# SATA.net
KiCad netlist of a schematic drawn in Altium Designer
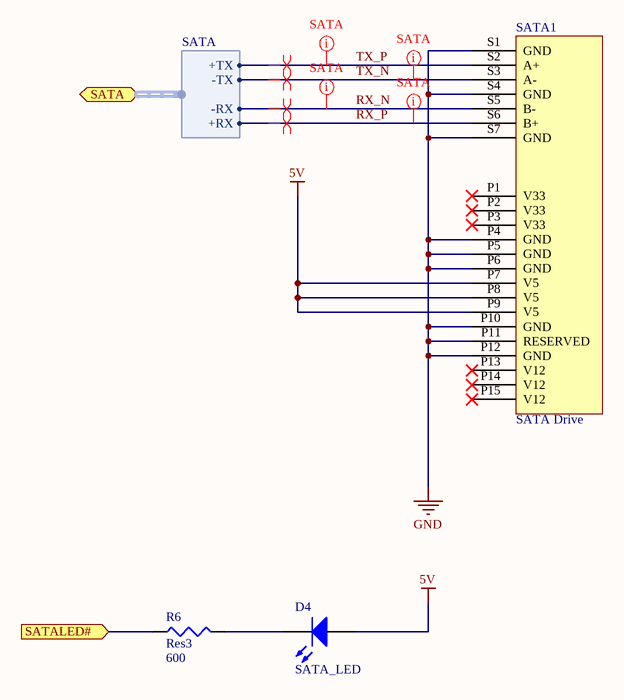
[diagram p0: SATA.SchDoc]

(export (version "E")
  (design (tool "Eeschema 10.0.6"))
  (components
    (comp (ref "D4")
      (value "SATA_LED")
      (footprint "0805")
      (description "Typical RED GaAs LED")
      (fields (field (name "PUBLISHER") "Altium Limited"))
      (libsource (lib "Miscellaneous Devices") (part "LED1"))
    )
    (comp (ref "R6")
      (value "Res3")
      (footprint "J1-0603")
      (description "Resistor")
      (fields (field (name "ALTIUM_VALUE") "600") (field (name "PUBLISHER") "Altium Limited"))
      (libsource (lib "Miscellaneous Devices") (part "Res3"))
    )
    (comp (ref "SATA1")
      (value "SATA Drive")
      (footprint "SATA COMB RECEPTICLE")
      (description "SATA HDD, FCI Part# 10029364")
      (libsource (lib "SATAConnectors") (part "SATA Drive"))
    )
  )
  (nets
    (net (code "2") (name "/RX_N") (class "Default")
      (node (ref "SATA1") (pin "S5") (pinfunction "B-_S5") (pintype "passive"))
    )
    (net (code "3") (name "/RX_P") (class "Default")
      (node (ref "SATA1") (pin "S6") (pinfunction "B+_S6") (pintype "passive"))
    )
    (net (code "4") (name "/SATALED#") (class "Default")
      (node (ref "R6") (pin "1") (pinfunction "1_1") (pintype "passive"))
    )
    (net (code "5") (name "/TX_N") (class "Default")
      (node (ref "SATA1") (pin "S3") (pinfunction "A-_S3") (pintype "passive"))
    )
    (net (code "6") (name "/TX_P") (class "Default")
      (node (ref "SATA1") (pin "S2") (pinfunction "A+_S2") (pintype "passive"))
    )
    (net (code "8") (name "5V") (class "Default")
      (node (ref "D4") (pin "1") (pinfunction "A_1") (pintype "passive"))
      (node (ref "SATA1") (pin "P7") (pinfunction "V5_P7") (pintype "passive"))
      (node (ref "SATA1") (pin "P8") (pinfunction "V5_P8") (pintype "passive"))
      (node (ref "SATA1") (pin "P9") (pinfunction "V5_P9") (pintype "passive"))
    )
    (net (code "9") (name "GND") (class "Default")
      (node (ref "SATA1") (pin "P10") (pinfunction "GND_P10") (pintype "passive"))
      (node (ref "SATA1") (pin "P11") (pinfunction "RESERVED_P11") (pintype "passive"))
      (node (ref "SATA1") (pin "P12") (pinfunction "GND_P12") (pintype "passive"))
      (node (ref "SATA1") (pin "P4") (pinfunction "GND_P4") (pintype "passive"))
      (node (ref "SATA1") (pin "P5") (pinfunction "GND_P5") (pintype "passive"))
      (node (ref "SATA1") (pin "P6") (pinfunction "GND_P6") (pintype "passive"))
      (node (ref "SATA1") (pin "S1") (pinfunction "GND_S1") (pintype "passive"))
      (node (ref "SATA1") (pin "S4") (pinfunction "GND_S4") (pintype "passive"))
      (node (ref "SATA1") (pin "S7") (pinfunction "GND_S7") (pintype "passive"))
    )
    (net (code "10") (name "Net-(D4-K)") (class "Default")
      (node (ref "D4") (pin "2") (pinfunction "K_2") (pintype "passive"))
      (node (ref "R6") (pin "2") (pinfunction "2_2") (pintype "passive"))
    )
    (net (code "11") (name "unconnected-(SATA1-V12-PadP13)") (class "Default")
      (node (ref "SATA1") (pin "P13") (pinfunction "V12_P13") (pintype "passive+no_connect"))
    )
    (net (code "12") (name "unconnected-(SATA1-V12-PadP14)") (class "Default")
      (node (ref "SATA1") (pin "P14") (pinfunction "V12_P14") (pintype "passive+no_connect"))
    )
    (net (code "13") (name "unconnected-(SATA1-V12-PadP15)") (class "Default")
      (node (ref "SATA1") (pin "P15") (pinfunction "V12_P15") (pintype "passive+no_connect"))
    )
    (net (code "14") (name "unconnected-(SATA1-V33-PadP1)") (class "Default")
      (node (ref "SATA1") (pin "P1") (pinfunction "V33_P1") (pintype "passive+no_connect"))
    )
    (net (code "15") (name "unconnected-(SATA1-V33-PadP2)") (class "Default")
      (node (ref "SATA1") (pin "P2") (pinfunction "V33_P2") (pintype "passive+no_connect"))
    )
    (net (code "16") (name "unconnected-(SATA1-V33-PadP3)") (class "Default")
      (node (ref "SATA1") (pin "P3") (pinfunction "V33_P3") (pintype "passive+no_connect"))
    )
  )
)
